# MSXIV_ConnectorTestingBoard.net
KiCad netlist of a schematic drawn in Altium Designer
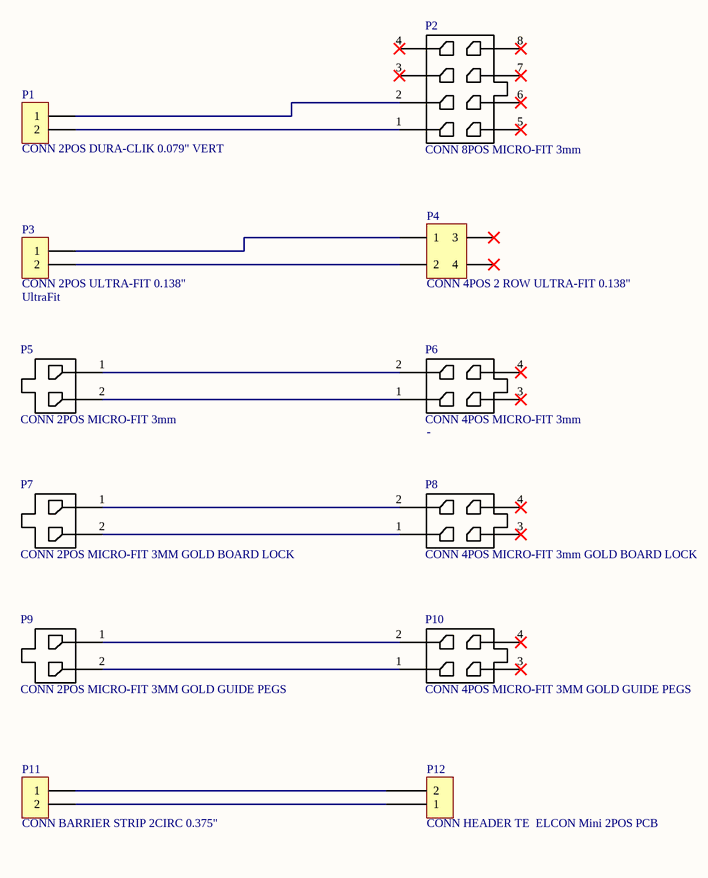
[diagram p0: MSXIV_ConnectorTestingBoard.SchDoc]

(export (version "E")
  (design (tool "Eeschema 10.0.6"))
  (components
    (comp (ref "P1")
      (value "CONN 2POS DURA-CLIK 0.079\" VERT")
      (footprint "CONN, 2POS Dura-Click Vertical")
      (description "2 Positions Header, Shrouded Connector 0.079\" (2.00mm) Surface Mount, Vertical Tin")
      (fields
        (field (name "MANUFACTURER") "Molex, LLC")
        (field (name "MANUFACTURER PART NUMBER") "5600200220")
        (field (name "SOURCE") "Schematic Diagrams.SchLib")
      )
      (libsource (lib "University of Waterloo - Solar Car Team") (part "Symbol"))
    )
    (comp (ref "P2")
      (value "CONN 8POS MICRO-FIT 3mm")
      (footprint "CONN, 8POS MICRO-FIT")
      (description "Connector Header Through Hole 6 position 0.118\" (3.00mm)")
      (fields
        (field (name "MANUFACTURER PART NUMBER") "0430450827")
        (field (name "MANUFACTURER") "Molex, LLC")
        (field (name "SOURCE") "Schematic Diagrams.SchLib")
      )
      (libsource (lib "University of Waterloo - Solar Car Team") (part "CONN 8POS MICRO-FIT 3mm"))
    )
    (comp (ref "P3")
      (value "CONN 2POS ULTRA-FIT 0.138\"")
      (footprint "CONN, 2POS ULTRA-FIT")
      (description "2 Positions Header, Shrouded Connector 0.138\" (3.50mm) Through Hole Gold")
      (fields
        (field (name "SERIES") "UltraFit")
        (field (name "VOLTAGE") "400V")
        (field (name "SOURCE") "Schematic Diagrams.SchLib")
      )
      (libsource (lib "University of Waterloo - Solar Car Team") (part "Symbol"))
    )
    (comp (ref "P4")
      (value "CONN 4POS 2 ROW ULTRA-FIT 0.138\"")
      (footprint "CONN, 4POS 2 ROW ULTRA-FIT")
      (description "Connector Header Through Hole 4 position 0.138\" (3.50mm)")
      (fields (field (name "SOURCE") "Schematic Diagrams.SchLib"))
      (libsource (lib "University of Waterloo - Solar Car Team") (part "CONN 4POS 2 ROW ULTRA-FIT 0.138{dblquote}"))
    )
    (comp (ref "P5")
      (value "CONN 2POS MICRO-FIT 3mm")
      (footprint "CONN 2POS MICRO-FIT 3mm-Footprint-1")
      (description "Conn Power HDR 2 POS 3mm Solder ST Thru-Hole 2 Terminal 1 Port Tray")
      (libsource (lib "University of Waterloo - Solar Car Team") (part "CONN 2POS MICRO-FIT 3mm"))
    )
    (comp (ref "P6")
      (value "CONN 4POS MICRO-FIT 3mm")
      (footprint "CONN 4POS MICROFIT (2x2)")
      (fields
        (field (name "CURRENT RATING") "-")
        (field (name "MANUFACTURER") "Molex, LLC")
        (field (name "MANUFACTURER PART NUMBER") "430450427")
        (field (name "SOURCE") "Schematic Diagrams.SchLib")
      )
      (libsource (lib "University of Waterloo - Solar Car Team") (part "CONN 4POS MICRO-FIT 3mm"))
    )
    (comp (ref "P7")
      (value "CONN 2POS MICRO-FIT 3MM GOLD BOARD LOCK")
      (footprint "CONN HEADER VERT 2POS 3MM GOLD BOARD LOCK-Footprint-1")
      (description "Conn Power HDR 2 POS 3mm Solder ST Thru-Hole 2 Terminal 1 Port Micro-Fit 3.0™ Tray")
      (libsource (lib "University of Waterloo - Solar Car Team") (part "CONN HEADER VERT 2POS 3MM GOLD BOARD LOCK"))
    )
    (comp (ref "P8")
      (value "CONN 4POS MICRO-FIT 3mm GOLD BOARD LOCK")
      (footprint "CONN 4POS MICRO-FIT 3mm GOLD BOARD LOCK-Footprint-1")
      (description "CONN HEADER VERT 4POS 3MM")
      (libsource (lib "University of Waterloo - Solar Car Team") (part "CONN 4POS MICRO-FIT 3mm GOLD BOARD LOCK"))
    )
    (comp (ref "P9")
      (value "CONN 2POS MICRO-FIT 3MM GOLD GUIDE PEGS")
      (footprint "CONN 2POS MICRO-FIT 3MM GOLD GUIDE PEGS-Footprint-1")
      (description "Conn; Rect; Header; 2 Cir; PCB; MicroFit 3.0; Vertical; Single; SMT; w/Peg; Gold")
      (libsource (lib "University of Waterloo - Solar Car Team") (part "CONN 2POS MICRO-FIT 3MM GOLD GUIDE PEGS"))
    )
    (comp (ref "P10")
      (value "CONN 4POS MICRO-FIT 3MM GOLD GUIDE PEGS")
      (footprint "CONN 4POS MICRO-FIT 3MM GOLD GUIDE PEGS-Footprint-1")
      (description "Conn Power HDR 4 POS 3mm Solder ST Thru-Hole 4 Terminal 1 Port Micro-Fit 3.0™ Tray")
      (libsource (lib "University of Waterloo - Solar Car Team") (part "CONN 4POS MICRO-FIT 3MM GOLD GUIDE PEGS"))
    )
    (comp (ref "P11")
      (value "CONN BARRIER STRIP 2CIRC 0.375\"")
      (footprint "TE_3-1437652-9")
      (description "Conn Power HDR 5 POS 3mm Solder ST Thru-Hole 5 Terminal 1 Port Micro-Fit 3.0™ Tray")
      (fields
        (field (name "MANUFACTURER") "TE Connectivity")
        (field (name "VOLTAGE") "300V")
        (field (name "SOURCE") "Schematic Diagrams.SchLib")
      )
      (libsource (lib "University of Waterloo - Solar Car Team") (part "CONN BARRIER STRIP 2CIRC 0.375{dblquote}"))
    )
    (comp (ref "P12")
      (value "CONN HEADER TE  ELCON Mini 2POS PCB")
      (footprint "CONN HEADER TE  ELCON Mini 2POS PCB-Footprint-1")
      (description "CONN HEADER 2POS PCB")
      (libsource (lib "University of Waterloo - Solar Car Team") (part "CONN HEADER TE  ELCON Mini 2POS PCB"))
    )
  )
  (nets
    (net (code "1") (name "Net-(P1-Pad1)") (class "Default")
      (node (ref "P1") (pin "1") (pinfunction "1_1") (pintype "passive"))
      (node (ref "P2") (pin "2") (pinfunction "2_2") (pintype "passive"))
    )
    (net (code "2") (name "Net-(P1-Pad2)") (class "Default")
      (node (ref "P1") (pin "2") (pinfunction "2_2") (pintype "passive"))
      (node (ref "P2") (pin "1") (pinfunction "1_1") (pintype "passive"))
    )
    (net (code "3") (name "Net-(P3-Pad1)") (class "Default")
      (node (ref "P3") (pin "1") (pinfunction "1_1") (pintype "passive"))
      (node (ref "P4") (pin "1") (pinfunction "1_1") (pintype "passive"))
    )
    (net (code "4") (name "Net-(P3-Pad2)") (class "Default")
      (node (ref "P3") (pin "2") (pinfunction "2_2") (pintype "passive"))
      (node (ref "P4") (pin "2") (pinfunction "2_2") (pintype "passive"))
    )
    (net (code "5") (name "Net-(P5-Pad1)") (class "Default")
      (node (ref "P5") (pin "1") (pinfunction "1_1") (pintype "passive"))
      (node (ref "P6") (pin "2") (pinfunction "2_2") (pintype "passive"))
    )
    (net (code "6") (name "Net-(P5-Pad2)") (class "Default")
      (node (ref "P5") (pin "2") (pinfunction "2_2") (pintype "passive"))
      (node (ref "P6") (pin "1") (pinfunction "1_1") (pintype "passive"))
    )
    (net (code "7") (name "Net-(P7-Pad1)") (class "Default")
      (node (ref "P7") (pin "1") (pinfunction "1_1") (pintype "passive"))
      (node (ref "P8") (pin "2") (pinfunction "2_2") (pintype "passive"))
    )
    (net (code "8") (name "Net-(P7-Pad2)") (class "Default")
      (node (ref "P7") (pin "2") (pinfunction "2_2") (pintype "passive"))
      (node (ref "P8") (pin "1") (pinfunction "1_1") (pintype "passive"))
    )
    (net (code "9") (name "Net-(P10-Pad1)") (class "Default")
      (node (ref "P10") (pin "1") (pinfunction "1_1") (pintype "passive"))
      (node (ref "P9") (pin "2") (pinfunction "2_2") (pintype "passive"))
    )
    (net (code "10") (name "Net-(P10-Pad2)") (class "Default")
      (node (ref "P10") (pin "2") (pinfunction "2_2") (pintype "passive"))
      (node (ref "P9") (pin "1") (pinfunction "1_1") (pintype "passive"))
    )
    (net (code "11") (name "Net-(P11-Pad1)") (class "Default")
      (node (ref "P11") (pin "1") (pinfunction "1_1") (pintype "passive"))
      (node (ref "P12") (pin "2") (pinfunction "2_2") (pintype "passive"))
    )
    (net (code "12") (name "Net-(P11-Pad2)") (class "Default")
      (node (ref "P11") (pin "2") (pinfunction "2_2") (pintype "passive"))
      (node (ref "P12") (pin "1") (pinfunction "1_1") (pintype "passive"))
    )
    (net (code "13") (name "unconnected-(P2-Pad3)") (class "Default")
      (node (ref "P2") (pin "3") (pinfunction "3_3") (pintype "passive+no_connect"))
    )
    (net (code "14") (name "unconnected-(P2-Pad4)") (class "Default")
      (node (ref "P2") (pin "4") (pinfunction "4_4") (pintype "passive+no_connect"))
    )
    (net (code "15") (name "unconnected-(P2-Pad5)") (class "Default")
      (node (ref "P2") (pin "5") (pinfunction "5_5") (pintype "passive+no_connect"))
    )
    (net (code "16") (name "unconnected-(P2-Pad6)") (class "Default")
      (node (ref "P2") (pin "6") (pinfunction "6_6") (pintype "passive+no_connect"))
    )
    (net (code "17") (name "unconnected-(P2-Pad7)") (class "Default")
      (node (ref "P2") (pin "7") (pinfunction "7_7") (pintype "passive+no_connect"))
    )
    (net (code "18") (name "unconnected-(P2-Pad8)") (class "Default")
      (node (ref "P2") (pin "8") (pinfunction "8_8") (pintype "passive+no_connect"))
    )
    (net (code "19") (name "unconnected-(P4-Pad3)") (class "Default")
      (node (ref "P4") (pin "3") (pinfunction "3_3") (pintype "passive+no_connect"))
    )
    (net (code "20") (name "unconnected-(P4-Pad4)") (class "Default")
      (node (ref "P4") (pin "4") (pinfunction "4_4") (pintype "passive+no_connect"))
    )
    (net (code "21") (name "unconnected-(P6-Pad3)") (class "Default")
      (node (ref "P6") (pin "3") (pinfunction "3_3") (pintype "passive+no_connect"))
    )
    (net (code "22") (name "unconnected-(P6-Pad4)") (class "Default")
      (node (ref "P6") (pin "4") (pinfunction "4_4") (pintype "passive+no_connect"))
    )
    (net (code "23") (name "unconnected-(P8-Pad3)") (class "Default")
      (node (ref "P8") (pin "3") (pinfunction "3_3") (pintype "passive+no_connect"))
    )
    (net (code "24") (name "unconnected-(P8-Pad4)") (class "Default")
      (node (ref "P8") (pin "4") (pinfunction "4_4") (pintype "passive+no_connect"))
    )
    (net (code "25") (name "unconnected-(P10-Pad3)") (class "Default")
      (node (ref "P10") (pin "3") (pinfunction "3_3") (pintype "passive+no_connect"))
    )
    (net (code "26") (name "unconnected-(P10-Pad4)") (class "Default")
      (node (ref "P10") (pin "4") (pinfunction "4_4") (pintype "passive+no_connect"))
    )
  )
)
